# display.net
KiCad netlist of a schematic drawn in EAGLE
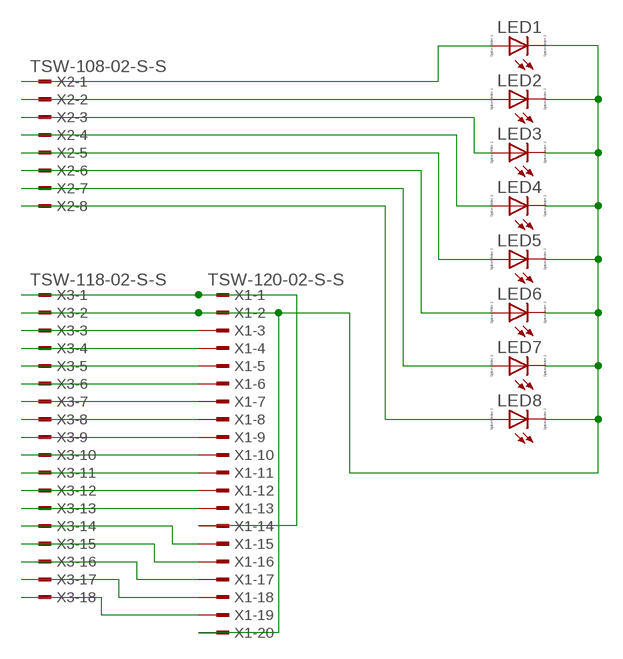
[diagram p0: schematic, sheet 1]

(export (version "E")
  (design (tool "Eeschema 10.0.6"))
  (components
    (comp (ref "LED1")
      (value "LED_ELD260")
      (footprint "eagle-import:LED_LD260")
      (libsource (lib "eagle-import") (part "LED_ELD260"))
    )
    (comp (ref "LED2")
      (value "LED_ELD260")
      (footprint "eagle-import:LED_LD260")
      (libsource (lib "eagle-import") (part "LED_ELD260"))
    )
    (comp (ref "LED3")
      (value "LED_ELD260")
      (footprint "eagle-import:LED_LD260")
      (libsource (lib "eagle-import") (part "LED_ELD260"))
    )
    (comp (ref "LED4")
      (value "LED_ELD260")
      (footprint "eagle-import:LED_LD260")
      (libsource (lib "eagle-import") (part "LED_ELD260"))
    )
    (comp (ref "LED5")
      (value "LED_ELD260")
      (footprint "eagle-import:LED_LD260")
      (libsource (lib "eagle-import") (part "LED_ELD260"))
    )
    (comp (ref "LED6")
      (value "LED_ELD260")
      (footprint "eagle-import:LED_LD260")
      (libsource (lib "eagle-import") (part "LED_ELD260"))
    )
    (comp (ref "LED7")
      (value "LED_ELD260")
      (footprint "eagle-import:LED_LD260")
      (libsource (lib "eagle-import") (part "LED_ELD260"))
    )
    (comp (ref "LED8")
      (value "LED_ELD260")
      (footprint "eagle-import:LED_LD260")
      (libsource (lib "eagle-import") (part "LED_ELD260"))
    )
    (comp (ref "X1")
      (value "TSW-120-02-S-S")
      (footprint "eagle-import:TSW-120-02-S-S")
      (libsource (lib "eagle-import") (part "TSW-120-02-S-S"))
    )
    (comp (ref "X2")
      (value "TSW-108-02-S-S")
      (footprint "eagle-import:TSW-108-02-S-S")
      (libsource (lib "eagle-import") (part "TSW-108-02-S-S"))
    )
    (comp (ref "X3")
      (value "TSW-118-02-S-S")
      (footprint "eagle-import:TSW-118-02-S-S")
      (libsource (lib "eagle-import") (part "TSW-118-02-S-S"))
    )
  )
  (nets
    (net (code "1") (name "Net-(LED1-C)") (class "Default")
      (node (ref "LED1") (pin "K") (pinfunction "C_K") (pintype "passive"))
      (node (ref "LED2") (pin "K") (pinfunction "C_K") (pintype "passive"))
      (node (ref "LED3") (pin "K") (pinfunction "C_K") (pintype "passive"))
      (node (ref "LED4") (pin "K") (pinfunction "C_K") (pintype "passive"))
      (node (ref "LED5") (pin "K") (pinfunction "C_K") (pintype "passive"))
      (node (ref "LED6") (pin "K") (pinfunction "C_K") (pintype "passive"))
      (node (ref "LED7") (pin "K") (pinfunction "C_K") (pintype "passive"))
      (node (ref "LED8") (pin "K") (pinfunction "C_K") (pintype "passive"))
      (node (ref "X1") (pin "2") (pinfunction "1_2") (pintype "passive"))
      (node (ref "X1") (pin "20") (pinfunction "1_20") (pintype "passive"))
      (node (ref "X3") (pin "2") (pinfunction "1_2") (pintype "passive"))
    )
    (net (code "2") (name "Net-(LED1-PadA)") (class "Default")
      (node (ref "LED1") (pin "A") (pinfunction "A_A") (pintype "passive"))
      (node (ref "X2") (pin "1") (pinfunction "1_1") (pintype "passive"))
    )
    (net (code "3") (name "Net-(X1B-1)") (class "Default")
      (node (ref "X1") (pin "10") (pinfunction "1_10") (pintype "passive"))
      (node (ref "X3") (pin "10") (pinfunction "1_10") (pintype "passive"))
    )
    (net (code "4") (name "Net-(X1C-1)") (class "Default")
      (node (ref "X1") (pin "11") (pinfunction "1_11") (pintype "passive"))
      (node (ref "X3") (pin "11") (pinfunction "1_11") (pintype "passive"))
    )
    (net (code "5") (name "Net-(X1D-1)") (class "Default")
      (node (ref "X1") (pin "12") (pinfunction "1_12") (pintype "passive"))
      (node (ref "X3") (pin "12") (pinfunction "1_12") (pintype "passive"))
    )
    (net (code "6") (name "Net-(X1E-1)") (class "Default")
      (node (ref "X1") (pin "13") (pinfunction "1_13") (pintype "passive"))
      (node (ref "X3") (pin "13") (pinfunction "1_13") (pintype "passive"))
    )
    (net (code "7") (name "Net-(X1F-1)") (class "Default")
      (node (ref "X1") (pin "1") (pinfunction "1_1") (pintype "passive"))
      (node (ref "X1") (pin "14") (pinfunction "1_14") (pintype "passive"))
      (node (ref "X3") (pin "1") (pinfunction "1_1") (pintype "passive"))
    )
    (net (code "8") (name "Net-(X1G-1)") (class "Default")
      (node (ref "X1") (pin "15") (pinfunction "1_15") (pintype "passive"))
      (node (ref "X3") (pin "14") (pinfunction "1_14") (pintype "passive"))
    )
    (net (code "9") (name "Net-(X1H-1)") (class "Default")
      (node (ref "X1") (pin "16") (pinfunction "1_16") (pintype "passive"))
      (node (ref "X3") (pin "15") (pinfunction "1_15") (pintype "passive"))
    )
    (net (code "10") (name "Net-(X1I-1)") (class "Default")
      (node (ref "X1") (pin "17") (pinfunction "1_17") (pintype "passive"))
      (node (ref "X3") (pin "16") (pinfunction "1_16") (pintype "passive"))
    )
    (net (code "11") (name "Net-(X1J-1)") (class "Default")
      (node (ref "X1") (pin "18") (pinfunction "1_18") (pintype "passive"))
      (node (ref "X3") (pin "17") (pinfunction "1_17") (pintype "passive"))
    )
    (net (code "12") (name "Net-(X1K-1)") (class "Default")
      (node (ref "X1") (pin "19") (pinfunction "1_19") (pintype "passive"))
      (node (ref "X3") (pin "18") (pinfunction "1_18") (pintype "passive"))
    )
    (net (code "13") (name "Net-(X1N-1)") (class "Default")
      (node (ref "X1") (pin "3") (pinfunction "1_3") (pintype "passive"))
      (node (ref "X3") (pin "3") (pinfunction "1_3") (pintype "passive"))
    )
    (net (code "14") (name "Net-(X1O-1)") (class "Default")
      (node (ref "X1") (pin "4") (pinfunction "1_4") (pintype "passive"))
      (node (ref "X3") (pin "4") (pinfunction "1_4") (pintype "passive"))
    )
    (net (code "15") (name "Net-(X1P-1)") (class "Default")
      (node (ref "X1") (pin "5") (pinfunction "1_5") (pintype "passive"))
      (node (ref "X3") (pin "5") (pinfunction "1_5") (pintype "passive"))
    )
    (net (code "16") (name "Net-(X1Q-1)") (class "Default")
      (node (ref "X1") (pin "6") (pinfunction "1_6") (pintype "passive"))
      (node (ref "X3") (pin "6") (pinfunction "1_6") (pintype "passive"))
    )
    (net (code "17") (name "Net-(X1R-1)") (class "Default")
      (node (ref "X1") (pin "7") (pinfunction "1_7") (pintype "passive"))
      (node (ref "X3") (pin "7") (pinfunction "1_7") (pintype "passive"))
    )
    (net (code "18") (name "Net-(X1S-1)") (class "Default")
      (node (ref "X1") (pin "8") (pinfunction "1_8") (pintype "passive"))
      (node (ref "X3") (pin "8") (pinfunction "1_8") (pintype "passive"))
    )
    (net (code "19") (name "Net-(X1T-1)") (class "Default")
      (node (ref "X1") (pin "9") (pinfunction "1_9") (pintype "passive"))
      (node (ref "X3") (pin "9") (pinfunction "1_9") (pintype "passive"))
    )
    (net (code "20") (name "Net-(X2B-1)") (class "Default")
      (node (ref "LED2") (pin "A") (pinfunction "A_A") (pintype "passive"))
      (node (ref "X2") (pin "2") (pinfunction "1_2") (pintype "passive"))
    )
    (net (code "21") (name "Net-(X2C-1)") (class "Default")
      (node (ref "LED3") (pin "A") (pinfunction "A_A") (pintype "passive"))
      (node (ref "X2") (pin "3") (pinfunction "1_3") (pintype "passive"))
    )
    (net (code "22") (name "Net-(X2D-1)") (class "Default")
      (node (ref "LED4") (pin "A") (pinfunction "A_A") (pintype "passive"))
      (node (ref "X2") (pin "4") (pinfunction "1_4") (pintype "passive"))
    )
    (net (code "23") (name "Net-(X2E-1)") (class "Default")
      (node (ref "LED5") (pin "A") (pinfunction "A_A") (pintype "passive"))
      (node (ref "X2") (pin "5") (pinfunction "1_5") (pintype "passive"))
    )
    (net (code "24") (name "Net-(X2F-1)") (class "Default")
      (node (ref "LED6") (pin "A") (pinfunction "A_A") (pintype "passive"))
      (node (ref "X2") (pin "6") (pinfunction "1_6") (pintype "passive"))
    )
    (net (code "25") (name "Net-(X2G-1)") (class "Default")
      (node (ref "LED7") (pin "A") (pinfunction "A_A") (pintype "passive"))
      (node (ref "X2") (pin "7") (pinfunction "1_7") (pintype "passive"))
    )
    (net (code "26") (name "Net-(X2H-1)") (class "Default")
      (node (ref "LED8") (pin "A") (pinfunction "A_A") (pintype "passive"))
      (node (ref "X2") (pin "8") (pinfunction "1_8") (pintype "passive"))
    )
  )
)
